# blink1micro-programming-jig.net
KiCad netlist of a schematic drawn in EAGLE
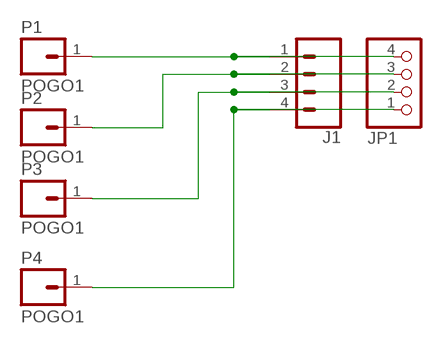
[diagram p0: schematic, sheet 1]

(export (version "E")
  (design (tool "Eeschema 10.0.6"))
  (components
    (comp (ref "J1")
      (value "CONN_04")
      (footprint "eagle-import:1X04")
      (libsource (lib "eagle-import") (part "CONN_04"))
    )
    (comp (ref "JP1")
      (value "PINHD-1X4/90")
      (footprint "eagle-import:1X04_90")
      (libsource (lib "eagle-import") (part "PINHD-1X4/90"))
    )
    (comp (ref "P1")
      (value "POGO1")
      (footprint "eagle-import:MILLMAX-0928-POGO-THRU")
      (libsource (lib "eagle-import") (part "POGO1"))
    )
    (comp (ref "P2")
      (value "POGO1")
      (footprint "eagle-import:MILLMAX-0928-POGO-THRU")
      (libsource (lib "eagle-import") (part "POGO1"))
    )
    (comp (ref "P3")
      (value "POGO1")
      (footprint "eagle-import:MILLMAX-0928-POGO-THRU")
      (libsource (lib "eagle-import") (part "POGO1"))
    )
    (comp (ref "P4")
      (value "POGO1")
      (footprint "eagle-import:MILLMAX-0928-POGO-THRU")
      (libsource (lib "eagle-import") (part "POGO1"))
    )
  )
  (nets
    (net (code "1") (name "Net-(J1-Pad1)") (class "Default")
      (node (ref "J1") (pin "1") (pinfunction "1_1") (pintype "passive"))
      (node (ref "JP1") (pin "4") (pinfunction "4_4") (pintype "passive"))
      (node (ref "P1") (pin "1") (pinfunction "1_1") (pintype "passive"))
    )
    (net (code "2") (name "Net-(J1-Pad2)") (class "Default")
      (node (ref "J1") (pin "2") (pinfunction "2_2") (pintype "passive"))
      (node (ref "JP1") (pin "3") (pinfunction "3_3") (pintype "passive"))
      (node (ref "P2") (pin "1") (pinfunction "1_1") (pintype "passive"))
    )
    (net (code "3") (name "Net-(J1-Pad3)") (class "Default")
      (node (ref "J1") (pin "3") (pinfunction "3_3") (pintype "passive"))
      (node (ref "JP1") (pin "2") (pinfunction "2_2") (pintype "passive"))
      (node (ref "P3") (pin "1") (pinfunction "1_1") (pintype "passive"))
    )
    (net (code "4") (name "Net-(J1-Pad4)") (class "Default")
      (node (ref "J1") (pin "4") (pinfunction "4_4") (pintype "passive"))
      (node (ref "JP1") (pin "1") (pinfunction "1_1") (pintype "passive"))
      (node (ref "P4") (pin "1") (pinfunction "1_1") (pintype "passive"))
    )
  )
)
